# panel5.net
KiCad netlist of a schematic drawn in Altium Designer
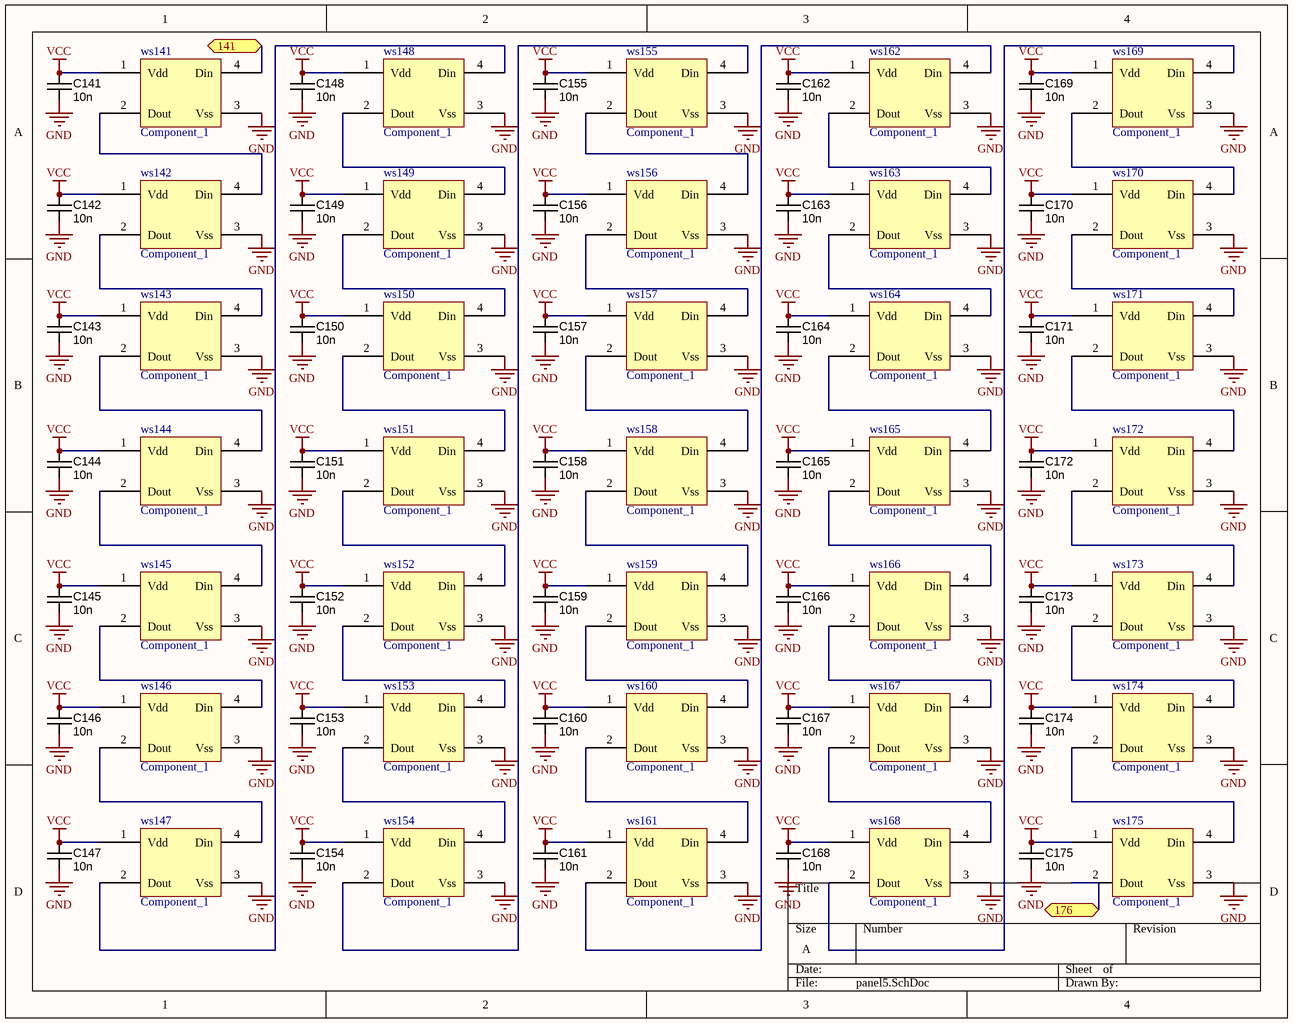
[diagram p0: panel5.SchDoc]

(export (version "E")
  (design (tool "Eeschema 10.0.6"))
  (components
    (comp (ref "C141")
      (value "10n")
      (footprint "CAPC1608X90N")
      (description "Capacitor SMD Cer 10nF 10% 100V X7R 0603")
      (fields
        (field (name "TOLERANCE") "±10%")
        (field (name "MANUFACTURER") "Murata Electronics North America")
      )
      (libsource (lib "PBL - Capacitors") (part "CAPC_10n_0603_X7R_100V_10%"))
    )
    (comp (ref "C142")
      (value "10n")
      (footprint "CAPC1608X90N")
      (description "Capacitor SMD Cer 10nF 10% 100V X7R 0603")
      (fields
        (field (name "TOLERANCE") "±10%")
        (field (name "MANUFACTURER") "Murata Electronics North America")
      )
      (libsource (lib "PBL - Capacitors") (part "CAPC_10n_0603_X7R_100V_10%"))
    )
    (comp (ref "C143")
      (value "10n")
      (footprint "CAPC1608X90N")
      (description "Capacitor SMD Cer 10nF 10% 100V X7R 0603")
      (fields
        (field (name "TOLERANCE") "±10%")
        (field (name "MANUFACTURER") "Murata Electronics North America")
      )
      (libsource (lib "PBL - Capacitors") (part "CAPC_10n_0603_X7R_100V_10%"))
    )
    (comp (ref "C144")
      (value "10n")
      (footprint "CAPC1608X90N")
      (description "Capacitor SMD Cer 10nF 10% 100V X7R 0603")
      (fields
        (field (name "TOLERANCE") "±10%")
        (field (name "MANUFACTURER") "Murata Electronics North America")
      )
      (libsource (lib "PBL - Capacitors") (part "CAPC_10n_0603_X7R_100V_10%"))
    )
    (comp (ref "C145")
      (value "10n")
      (footprint "CAPC1608X90N")
      (description "Capacitor SMD Cer 10nF 10% 100V X7R 0603")
      (fields
        (field (name "TOLERANCE") "±10%")
        (field (name "MANUFACTURER") "Murata Electronics North America")
      )
      (libsource (lib "PBL - Capacitors") (part "CAPC_10n_0603_X7R_100V_10%"))
    )
    (comp (ref "C146")
      (value "10n")
      (footprint "CAPC1608X90N")
      (description "Capacitor SMD Cer 10nF 10% 100V X7R 0603")
      (fields
        (field (name "TOLERANCE") "±10%")
        (field (name "MANUFACTURER") "Murata Electronics North America")
      )
      (libsource (lib "PBL - Capacitors") (part "CAPC_10n_0603_X7R_100V_10%"))
    )
    (comp (ref "C147")
      (value "10n")
      (footprint "CAPC1608X90N")
      (description "Capacitor SMD Cer 10nF 10% 100V X7R 0603")
      (fields
        (field (name "TOLERANCE") "±10%")
        (field (name "MANUFACTURER") "Murata Electronics North America")
      )
      (libsource (lib "PBL - Capacitors") (part "CAPC_10n_0603_X7R_100V_10%"))
    )
    (comp (ref "C148")
      (value "10n")
      (footprint "CAPC1608X90N")
      (description "Capacitor SMD Cer 10nF 10% 100V X7R 0603")
      (fields
        (field (name "TOLERANCE") "±10%")
        (field (name "MANUFACTURER") "Murata Electronics North America")
      )
      (libsource (lib "PBL - Capacitors") (part "CAPC_10n_0603_X7R_100V_10%"))
    )
    (comp (ref "C149")
      (value "10n")
      (footprint "CAPC1608X90N")
      (description "Capacitor SMD Cer 10nF 10% 100V X7R 0603")
      (fields
        (field (name "TOLERANCE") "±10%")
        (field (name "MANUFACTURER") "Murata Electronics North America")
      )
      (libsource (lib "PBL - Capacitors") (part "CAPC_10n_0603_X7R_100V_10%"))
    )
    (comp (ref "C150")
      (value "10n")
      (footprint "CAPC1608X90N")
      (description "Capacitor SMD Cer 10nF 10% 100V X7R 0603")
      (fields
        (field (name "TOLERANCE") "±10%")
        (field (name "MANUFACTURER") "Murata Electronics North America")
      )
      (libsource (lib "PBL - Capacitors") (part "CAPC_10n_0603_X7R_100V_10%"))
    )
    (comp (ref "C151")
      (value "10n")
      (footprint "CAPC1608X90N")
      (description "Capacitor SMD Cer 10nF 10% 100V X7R 0603")
      (fields
        (field (name "TOLERANCE") "±10%")
        (field (name "MANUFACTURER") "Murata Electronics North America")
      )
      (libsource (lib "PBL - Capacitors") (part "CAPC_10n_0603_X7R_100V_10%"))
    )
    (comp (ref "C152")
      (value "10n")
      (footprint "CAPC1608X90N")
      (description "Capacitor SMD Cer 10nF 10% 100V X7R 0603")
      (fields
        (field (name "TOLERANCE") "±10%")
        (field (name "MANUFACTURER") "Murata Electronics North America")
      )
      (libsource (lib "PBL - Capacitors") (part "CAPC_10n_0603_X7R_100V_10%"))
    )
    (comp (ref "C153")
      (value "10n")
      (footprint "CAPC1608X90N")
      (description "Capacitor SMD Cer 10nF 10% 100V X7R 0603")
      (fields
        (field (name "TOLERANCE") "±10%")
        (field (name "MANUFACTURER") "Murata Electronics North America")
      )
      (libsource (lib "PBL - Capacitors") (part "CAPC_10n_0603_X7R_100V_10%"))
    )
    (comp (ref "C154")
      (value "10n")
      (footprint "CAPC1608X90N")
      (description "Capacitor SMD Cer 10nF 10% 100V X7R 0603")
      (fields
        (field (name "TOLERANCE") "±10%")
        (field (name "MANUFACTURER") "Murata Electronics North America")
      )
      (libsource (lib "PBL - Capacitors") (part "CAPC_10n_0603_X7R_100V_10%"))
    )
    (comp (ref "C155")
      (value "10n")
      (footprint "CAPC1608X90N")
      (description "Capacitor SMD Cer 10nF 10% 100V X7R 0603")
      (fields
        (field (name "TOLERANCE") "±10%")
        (field (name "MANUFACTURER") "Murata Electronics North America")
      )
      (libsource (lib "PBL - Capacitors") (part "CAPC_10n_0603_X7R_100V_10%"))
    )
    (comp (ref "C156")
      (value "10n")
      (footprint "CAPC1608X90N")
      (description "Capacitor SMD Cer 10nF 10% 100V X7R 0603")
      (fields
        (field (name "TOLERANCE") "±10%")
        (field (name "MANUFACTURER") "Murata Electronics North America")
      )
      (libsource (lib "PBL - Capacitors") (part "CAPC_10n_0603_X7R_100V_10%"))
    )
    (comp (ref "C157")
      (value "10n")
      (footprint "CAPC1608X90N")
      (description "Capacitor SMD Cer 10nF 10% 100V X7R 0603")
      (fields
        (field (name "TOLERANCE") "±10%")
        (field (name "MANUFACTURER") "Murata Electronics North America")
      )
      (libsource (lib "PBL - Capacitors") (part "CAPC_10n_0603_X7R_100V_10%"))
    )
    (comp (ref "C158")
      (value "10n")
      (footprint "CAPC1608X90N")
      (description "Capacitor SMD Cer 10nF 10% 100V X7R 0603")
      (fields
        (field (name "TOLERANCE") "±10%")
        (field (name "MANUFACTURER") "Murata Electronics North America")
      )
      (libsource (lib "PBL - Capacitors") (part "CAPC_10n_0603_X7R_100V_10%"))
    )
    (comp (ref "C159")
      (value "10n")
      (footprint "CAPC1608X90N")
      (description "Capacitor SMD Cer 10nF 10% 100V X7R 0603")
      (fields
        (field (name "TOLERANCE") "±10%")
        (field (name "MANUFACTURER") "Murata Electronics North America")
      )
      (libsource (lib "PBL - Capacitors") (part "CAPC_10n_0603_X7R_100V_10%"))
    )
    (comp (ref "C160")
      (value "10n")
      (footprint "CAPC1608X90N")
      (description "Capacitor SMD Cer 10nF 10% 100V X7R 0603")
      (fields
        (field (name "TOLERANCE") "±10%")
        (field (name "MANUFACTURER") "Murata Electronics North America")
      )
      (libsource (lib "PBL - Capacitors") (part "CAPC_10n_0603_X7R_100V_10%"))
    )
    (comp (ref "C161")
      (value "10n")
      (footprint "CAPC1608X90N")
      (description "Capacitor SMD Cer 10nF 10% 100V X7R 0603")
      (fields
        (field (name "TOLERANCE") "±10%")
        (field (name "MANUFACTURER") "Murata Electronics North America")
      )
      (libsource (lib "PBL - Capacitors") (part "CAPC_10n_0603_X7R_100V_10%"))
    )
    (comp (ref "C162")
      (value "10n")
      (footprint "CAPC1608X90N")
      (description "Capacitor SMD Cer 10nF 10% 100V X7R 0603")
      (fields
        (field (name "TOLERANCE") "±10%")
        (field (name "MANUFACTURER") "Murata Electronics North America")
      )
      (libsource (lib "PBL - Capacitors") (part "CAPC_10n_0603_X7R_100V_10%"))
    )
    (comp (ref "C163")
      (value "10n")
      (footprint "CAPC1608X90N")
      (description "Capacitor SMD Cer 10nF 10% 100V X7R 0603")
      (fields
        (field (name "TOLERANCE") "±10%")
        (field (name "MANUFACTURER") "Murata Electronics North America")
      )
      (libsource (lib "PBL - Capacitors") (part "CAPC_10n_0603_X7R_100V_10%"))
    )
    (comp (ref "C164")
      (value "10n")
      (footprint "CAPC1608X90N")
      (description "Capacitor SMD Cer 10nF 10% 100V X7R 0603")
      (fields
        (field (name "TOLERANCE") "±10%")
        (field (name "MANUFACTURER") "Murata Electronics North America")
      )
      (libsource (lib "PBL - Capacitors") (part "CAPC_10n_0603_X7R_100V_10%"))
    )
    (comp (ref "C165")
      (value "10n")
      (footprint "CAPC1608X90N")
      (description "Capacitor SMD Cer 10nF 10% 100V X7R 0603")
      (fields
        (field (name "TOLERANCE") "±10%")
        (field (name "MANUFACTURER") "Murata Electronics North America")
      )
      (libsource (lib "PBL - Capacitors") (part "CAPC_10n_0603_X7R_100V_10%"))
    )
    (comp (ref "C166")
      (value "10n")
      (footprint "CAPC1608X90N")
      (description "Capacitor SMD Cer 10nF 10% 100V X7R 0603")
      (fields
        (field (name "TOLERANCE") "±10%")
        (field (name "MANUFACTURER") "Murata Electronics North America")
      )
      (libsource (lib "PBL - Capacitors") (part "CAPC_10n_0603_X7R_100V_10%"))
    )
    (comp (ref "C167")
      (value "10n")
      (footprint "CAPC1608X90N")
      (description "Capacitor SMD Cer 10nF 10% 100V X7R 0603")
      (fields
        (field (name "TOLERANCE") "±10%")
        (field (name "MANUFACTURER") "Murata Electronics North America")
      )
      (libsource (lib "PBL - Capacitors") (part "CAPC_10n_0603_X7R_100V_10%"))
    )
    (comp (ref "C168")
      (value "10n")
      (footprint "CAPC1608X90N")
      (description "Capacitor SMD Cer 10nF 10% 100V X7R 0603")
      (fields
        (field (name "TOLERANCE") "±10%")
        (field (name "MANUFACTURER") "Murata Electronics North America")
      )
      (libsource (lib "PBL - Capacitors") (part "CAPC_10n_0603_X7R_100V_10%"))
    )
    (comp (ref "C169")
      (value "10n")
      (footprint "CAPC1608X90N")
      (description "Capacitor SMD Cer 10nF 10% 100V X7R 0603")
      (fields
        (field (name "TOLERANCE") "±10%")
        (field (name "MANUFACTURER") "Murata Electronics North America")
      )
      (libsource (lib "PBL - Capacitors") (part "CAPC_10n_0603_X7R_100V_10%"))
    )
    (comp (ref "C170")
      (value "10n")
      (footprint "CAPC1608X90N")
      (description "Capacitor SMD Cer 10nF 10% 100V X7R 0603")
      (fields
        (field (name "TOLERANCE") "±10%")
        (field (name "MANUFACTURER") "Murata Electronics North America")
      )
      (libsource (lib "PBL - Capacitors") (part "CAPC_10n_0603_X7R_100V_10%"))
    )
    (comp (ref "C171")
      (value "10n")
      (footprint "CAPC1608X90N")
      (description "Capacitor SMD Cer 10nF 10% 100V X7R 0603")
      (fields
        (field (name "TOLERANCE") "±10%")
        (field (name "MANUFACTURER") "Murata Electronics North America")
      )
      (libsource (lib "PBL - Capacitors") (part "CAPC_10n_0603_X7R_100V_10%"))
    )
    (comp (ref "C172")
      (value "10n")
      (footprint "CAPC1608X90N")
      (description "Capacitor SMD Cer 10nF 10% 100V X7R 0603")
      (fields
        (field (name "TOLERANCE") "±10%")
        (field (name "MANUFACTURER") "Murata Electronics North America")
      )
      (libsource (lib "PBL - Capacitors") (part "CAPC_10n_0603_X7R_100V_10%"))
    )
    (comp (ref "C173")
      (value "10n")
      (footprint "CAPC1608X90N")
      (description "Capacitor SMD Cer 10nF 10% 100V X7R 0603")
      (fields
        (field (name "TOLERANCE") "±10%")
        (field (name "MANUFACTURER") "Murata Electronics North America")
      )
      (libsource (lib "PBL - Capacitors") (part "CAPC_10n_0603_X7R_100V_10%"))
    )
    (comp (ref "C174")
      (value "10n")
      (footprint "CAPC1608X90N")
      (description "Capacitor SMD Cer 10nF 10% 100V X7R 0603")
      (fields
        (field (name "TOLERANCE") "±10%")
        (field (name "MANUFACTURER") "Murata Electronics North America")
      )
      (libsource (lib "PBL - Capacitors") (part "CAPC_10n_0603_X7R_100V_10%"))
    )
    (comp (ref "C175")
      (value "10n")
      (footprint "CAPC1608X90N")
      (description "Capacitor SMD Cer 10nF 10% 100V X7R 0603")
      (fields
        (field (name "TOLERANCE") "±10%")
        (field (name "MANUFACTURER") "Murata Electronics North America")
      )
      (libsource (lib "PBL - Capacitors") (part "CAPC_10n_0603_X7R_100V_10%"))
    )
    (comp (ref "ws141")
      (value "Component_1")
      (footprint "SOP4")
      (libsource (lib "ws2812b") (part "Component_1"))
    )
    (comp (ref "ws142")
      (value "Component_1")
      (footprint "SOP4")
      (libsource (lib "ws2812b") (part "Component_1"))
    )
    (comp (ref "ws143")
      (value "Component_1")
      (footprint "SOP4")
      (libsource (lib "ws2812b") (part "Component_1"))
    )
    (comp (ref "ws144")
      (value "Component_1")
      (footprint "SOP4")
      (libsource (lib "ws2812b") (part "Component_1"))
    )
    (comp (ref "ws145")
      (value "Component_1")
      (footprint "SOP4")
      (libsource (lib "ws2812b") (part "Component_1"))
    )
    (comp (ref "ws146")
      (value "Component_1")
      (footprint "SOP4")
      (libsource (lib "ws2812b") (part "Component_1"))
    )
    (comp (ref "ws147")
      (value "Component_1")
      (footprint "SOP4")
      (libsource (lib "ws2812b") (part "Component_1"))
    )
    (comp (ref "ws148")
      (value "Component_1")
      (footprint "SOP4")
      (libsource (lib "ws2812b") (part "Component_1"))
    )
    (comp (ref "ws149")
      (value "Component_1")
      (footprint "SOP4")
      (libsource (lib "ws2812b") (part "Component_1"))
    )
    (comp (ref "ws150")
      (value "Component_1")
      (footprint "SOP4")
      (libsource (lib "ws2812b") (part "Component_1"))
    )
    (comp (ref "ws151")
      (value "Component_1")
      (footprint "SOP4")
      (libsource (lib "ws2812b") (part "Component_1"))
    )
    (comp (ref "ws152")
      (value "Component_1")
      (footprint "SOP4")
      (libsource (lib "ws2812b") (part "Component_1"))
    )
    (comp (ref "ws153")
      (value "Component_1")
      (footprint "SOP4")
      (libsource (lib "ws2812b") (part "Component_1"))
    )
    (comp (ref "ws154")
      (value "Component_1")
      (footprint "SOP4")
      (libsource (lib "ws2812b") (part "Component_1"))
    )
    (comp (ref "ws155")
      (value "Component_1")
      (footprint "SOP4")
      (libsource (lib "ws2812b") (part "Component_1"))
    )
    (comp (ref "ws156")
      (value "Component_1")
      (footprint "SOP4")
      (libsource (lib "ws2812b") (part "Component_1"))
    )
    (comp (ref "ws157")
      (value "Component_1")
      (footprint "SOP4")
      (libsource (lib "ws2812b") (part "Component_1"))
    )
    (comp (ref "ws158")
      (value "Component_1")
      (footprint "SOP4")
      (libsource (lib "ws2812b") (part "Component_1"))
    )
    (comp (ref "ws159")
      (value "Component_1")
      (footprint "SOP4")
      (libsource (lib "ws2812b") (part "Component_1"))
    )
    (comp (ref "ws160")
      (value "Component_1")
      (footprint "SOP4")
      (libsource (lib "ws2812b") (part "Component_1"))
    )
    (comp (ref "ws161")
      (value "Component_1")
      (footprint "SOP4")
      (libsource (lib "ws2812b") (part "Component_1"))
    )
    (comp (ref "ws162")
      (value "Component_1")
      (footprint "SOP4")
      (libsource (lib "ws2812b") (part "Component_1"))
    )
    (comp (ref "ws163")
      (value "Component_1")
      (footprint "SOP4")
      (libsource (lib "ws2812b") (part "Component_1"))
    )
    (comp (ref "ws164")
      (value "Component_1")
      (footprint "SOP4")
      (libsource (lib "ws2812b") (part "Component_1"))
    )
    (comp (ref "ws165")
      (value "Component_1")
      (footprint "SOP4")
      (libsource (lib "ws2812b") (part "Component_1"))
    )
    (comp (ref "ws166")
      (value "Component_1")
      (footprint "SOP4")
      (libsource (lib "ws2812b") (part "Component_1"))
    )
    (comp (ref "ws167")
      (value "Component_1")
      (footprint "SOP4")
      (libsource (lib "ws2812b") (part "Component_1"))
    )
    (comp (ref "ws168")
      (value "Component_1")
      (footprint "SOP4")
      (libsource (lib "ws2812b") (part "Component_1"))
    )
    (comp (ref "ws169")
      (value "Component_1")
      (footprint "SOP4")
      (libsource (lib "ws2812b") (part "Component_1"))
    )
    (comp (ref "ws170")
      (value "Component_1")
      (footprint "SOP4")
      (libsource (lib "ws2812b") (part "Component_1"))
    )
    (comp (ref "ws171")
      (value "Component_1")
      (footprint "SOP4")
      (libsource (lib "ws2812b") (part "Component_1"))
    )
    (comp (ref "ws172")
      (value "Component_1")
      (footprint "SOP4")
      (libsource (lib "ws2812b") (part "Component_1"))
    )
    (comp (ref "ws173")
      (value "Component_1")
      (footprint "SOP4")
      (libsource (lib "ws2812b") (part "Component_1"))
    )
    (comp (ref "ws174")
      (value "Component_1")
      (footprint "SOP4")
      (libsource (lib "ws2812b") (part "Component_1"))
    )
    (comp (ref "ws175")
      (value "Component_1")
      (footprint "SOP4")
      (libsource (lib "ws2812b") (part "Component_1"))
    )
  )
  (nets
    (net (code "1") (name "/141") (class "Default")
      (node (ref "ws141") (pin "4") (pinfunction "Din_4") (pintype "passive"))
    )
    (net (code "2") (name "/176") (class "Default")
      (node (ref "ws175") (pin "2") (pinfunction "Dout_2") (pintype "passive"))
    )
    (net (code "3") (name "GND") (class "Default")
      (node (ref "C141") (pin "2") (pintype "passive"))
      (node (ref "C142") (pin "2") (pintype "passive"))
      (node (ref "C143") (pin "2") (pintype "passive"))
      (node (ref "C144") (pin "2") (pintype "passive"))
      (node (ref "C145") (pin "2") (pintype "passive"))
      (node (ref "C146") (pin "2") (pintype "passive"))
      (node (ref "C147") (pin "2") (pintype "passive"))
      (node (ref "C148") (pin "2") (pintype "passive"))
      (node (ref "C149") (pin "2") (pintype "passive"))
      (node (ref "C150") (pin "2") (pintype "passive"))
      (node (ref "C151") (pin "2") (pintype "passive"))
      (node (ref "C152") (pin "2") (pintype "passive"))
      (node (ref "C153") (pin "2") (pintype "passive"))
      (node (ref "C154") (pin "2") (pintype "passive"))
      (node (ref "C155") (pin "2") (pintype "passive"))
      (node (ref "C156") (pin "2") (pintype "passive"))
      (node (ref "C157") (pin "2") (pintype "passive"))
      (node (ref "C158") (pin "2") (pintype "passive"))
      (node (ref "C159") (pin "2") (pintype "passive"))
      (node (ref "C160") (pin "2") (pintype "passive"))
      (node (ref "C161") (pin "2") (pintype "passive"))
      (node (ref "C162") (pin "2") (pintype "passive"))
      (node (ref "C163") (pin "2") (pintype "passive"))
      (node (ref "C164") (pin "2") (pintype "passive"))
      (node (ref "C165") (pin "2") (pintype "passive"))
      (node (ref "C166") (pin "2") (pintype "passive"))
      (node (ref "C167") (pin "2") (pintype "passive"))
      (node (ref "C168") (pin "2") (pintype "passive"))
      (node (ref "C169") (pin "2") (pintype "passive"))
      (node (ref "C170") (pin "2") (pintype "passive"))
      (node (ref "C171") (pin "2") (pintype "passive"))
      (node (ref "C172") (pin "2") (pintype "passive"))
      (node (ref "C173") (pin "2") (pintype "passive"))
      (node (ref "C174") (pin "2") (pintype "passive"))
      (node (ref "C175") (pin "2") (pintype "passive"))
      (node (ref "ws141") (pin "3") (pinfunction "Vss_3") (pintype "passive"))
      (node (ref "ws142") (pin "3") (pinfunction "Vss_3") (pintype "passive"))
      (node (ref "ws143") (pin "3") (pinfunction "Vss_3") (pintype "passive"))
      (node (ref "ws144") (pin "3") (pinfunction "Vss_3") (pintype "passive"))
      (node (ref "ws145") (pin "3") (pinfunction "Vss_3") (pintype "passive"))
      (node (ref "ws146") (pin "3") (pinfunction "Vss_3") (pintype "passive"))
      (node (ref "ws147") (pin "3") (pinfunction "Vss_3") (pintype "passive"))
      (node (ref "ws148") (pin "3") (pinfunction "Vss_3") (pintype "passive"))
      (node (ref "ws149") (pin "3") (pinfunction "Vss_3") (pintype "passive"))
      (node (ref "ws150") (pin "3") (pinfunction "Vss_3") (pintype "passive"))
      (node (ref "ws151") (pin "3") (pinfunction "Vss_3") (pintype "passive"))
      (node (ref "ws152") (pin "3") (pinfunction "Vss_3") (pintype "passive"))
      (node (ref "ws153") (pin "3") (pinfunction "Vss_3") (pintype "passive"))
      (node (ref "ws154") (pin "3") (pinfunction "Vss_3") (pintype "passive"))
      (node (ref "ws155") (pin "3") (pinfunction "Vss_3") (pintype "passive"))
      (node (ref "ws156") (pin "3") (pinfunction "Vss_3") (pintype "passive"))
      (node (ref "ws157") (pin "3") (pinfunction "Vss_3") (pintype "passive"))
      (node (ref "ws158") (pin "3") (pinfunction "Vss_3") (pintype "passive"))
      (node (ref "ws159") (pin "3") (pinfunction "Vss_3") (pintype "passive"))
      (node (ref "ws160") (pin "3") (pinfunction "Vss_3") (pintype "passive"))
      (node (ref "ws161") (pin "3") (pinfunction "Vss_3") (pintype "passive"))
      (node (ref "ws162") (pin "3") (pinfunction "Vss_3") (pintype "passive"))
      (node (ref "ws163") (pin "3") (pinfunction "Vss_3") (pintype "passive"))
      (node (ref "ws164") (pin "3") (pinfunction "Vss_3") (pintype "passive"))
      (node (ref "ws165") (pin "3") (pinfunction "Vss_3") (pintype "passive"))
      (node (ref "ws166") (pin "3") (pinfunction "Vss_3") (pintype "passive"))
      (node (ref "ws167") (pin "3") (pinfunction "Vss_3") (pintype "passive"))
      (node (ref "ws168") (pin "3") (pinfunction "Vss_3") (pintype "passive"))
      (node (ref "ws169") (pin "3") (pinfunction "Vss_3") (pintype "passive"))
      (node (ref "ws170") (pin "3") (pinfunction "Vss_3") (pintype "passive"))
      (node (ref "ws171") (pin "3") (pinfunction "Vss_3") (pintype "passive"))
      (node (ref "ws172") (pin "3") (pinfunction "Vss_3") (pintype "passive"))
      (node (ref "ws173") (pin "3") (pinfunction "Vss_3") (pintype "passive"))
      (node (ref "ws174") (pin "3") (pinfunction "Vss_3") (pintype "passive"))
      (node (ref "ws175") (pin "3") (pinfunction "Vss_3") (pintype "passive"))
    )
    (net (code "4") (name "Net-(ws141-Dout)") (class "Default")
      (node (ref "ws141") (pin "2") (pinfunction "Dout_2") (pintype "passive"))
      (node (ref "ws142") (pin "4") (pinfunction "Din_4") (pintype "passive"))
    )
    (net (code "5") (name "Net-(ws142-Dout)") (class "Default")
      (node (ref "ws142") (pin "2") (pinfunction "Dout_2") (pintype "passive"))
      (node (ref "ws143") (pin "4") (pinfunction "Din_4") (pintype "passive"))
    )
    (net (code "6") (name "Net-(ws143-Dout)") (class "Default")
      (node (ref "ws143") (pin "2") (pinfunction "Dout_2") (pintype "passive"))
      (node (ref "ws144") (pin "4") (pinfunction "Din_4") (pintype "passive"))
    )
    (net (code "7") (name "Net-(ws144-Dout)") (class "Default")
      (node (ref "ws144") (pin "2") (pinfunction "Dout_2") (pintype "passive"))
      (node (ref "ws145") (pin "4") (pinfunction "Din_4") (pintype "passive"))
    )
    (net (code "8") (name "Net-(ws145-Dout)") (class "Default")
      (node (ref "ws145") (pin "2") (pinfunction "Dout_2") (pintype "passive"))
      (node (ref "ws146") (pin "4") (pinfunction "Din_4") (pintype "passive"))
    )
    (net (code "9") (name "Net-(ws146-Dout)") (class "Default")
      (node (ref "ws146") (pin "2") (pinfunction "Dout_2") (pintype "passive"))
      (node (ref "ws147") (pin "4") (pinfunction "Din_4") (pintype "passive"))
    )
    (net (code "10") (name "Net-(ws147-Dout)") (class "Default")
      (node (ref "ws147") (pin "2") (pinfunction "Dout_2") (pintype "passive"))
      (node (ref "ws148") (pin "4") (pinfunction "Din_4") (pintype "passive"))
    )
    (net (code "11") (name "Net-(ws148-Dout)") (class "Default")
      (node (ref "ws148") (pin "2") (pinfunction "Dout_2") (pintype "passive"))
      (node (ref "ws149") (pin "4") (pinfunction "Din_4") (pintype "passive"))
    )
    (net (code "12") (name "Net-(ws149-Dout)") (class "Default")
      (node (ref "ws149") (pin "2") (pinfunction "Dout_2") (pintype "passive"))
      (node (ref "ws150") (pin "4") (pinfunction "Din_4") (pintype "passive"))
    )
    (net (code "13") (name "Net-(ws150-Dout)") (class "Default")
      (node (ref "ws150") (pin "2") (pinfunction "Dout_2") (pintype "passive"))
      (node (ref "ws151") (pin "4") (pinfunction "Din_4") (pintype "passive"))
    )
    (net (code "14") (name "Net-(ws151-Dout)") (class "Default")
      (node (ref "ws151") (pin "2") (pinfunction "Dout_2") (pintype "passive"))
      (node (ref "ws152") (pin "4") (pinfunction "Din_4") (pintype "passive"))
    )
    (net (code "15") (name "Net-(ws152-Dout)") (class "Default")
      (node (ref "ws152") (pin "2") (pinfunction "Dout_2") (pintype "passive"))
      (node (ref "ws153") (pin "4") (pinfunction "Din_4") (pintype "passive"))
    )
    (net (code "16") (name "Net-(ws153-Dout)") (class "Default")
      (node (ref "ws153") (pin "2") (pinfunction "Dout_2") (pintype "passive"))
      (node (ref "ws154") (pin "4") (pinfunction "Din_4") (pintype "passive"))
    )
    (net (code "17") (name "Net-(ws154-Dout)") (class "Default")
      (node (ref "ws154") (pin "2") (pinfunction "Dout_2") (pintype "passive"))
      (node (ref "ws155") (pin "4") (pinfunction "Din_4") (pintype "passive"))
    )
    (net (code "18") (name "Net-(ws155-Dout)") (class "Default")
      (node (ref "ws155") (pin "2") (pinfunction "Dout_2") (pintype "passive"))
      (node (ref "ws156") (pin "4") (pinfunction "Din_4") (pintype "passive"))
    )
    (net (code "19") (name "Net-(ws156-Dout)") (class "Default")
      (node (ref "ws156") (pin "2") (pinfunction "Dout_2") (pintype "passive"))
      (node (ref "ws157") (pin "4") (pinfunction "Din_4") (pintype "passive"))
    )
    (net (code "20") (name "Net-(ws157-Dout)") (class "Default")
      (node (ref "ws157") (pin "2") (pinfunction "Dout_2") (pintype "passive"))
      (node (ref "ws158") (pin "4") (pinfunction "Din_4") (pintype "passive"))
    )
    (net (code "21") (name "Net-(ws158-Dout)") (class "Default")
      (node (ref "ws158") (pin "2") (pinfunction "Dout_2") (pintype "passive"))
      (node (ref "ws159") (pin "4") (pinfunction "Din_4") (pintype "passive"))
    )
    (net (code "22") (name "Net-(ws159-Dout)") (class "Default")
      (node (ref "ws159") (pin "2") (pinfunction "Dout_2") (pintype "passive"))
      (node (ref "ws160") (pin "4") (pinfunction "Din_4") (pintype "passive"))
    )
    (net (code "23") (name "Net-(ws160-Dout)") (class "Default")
      (node (ref "ws160") (pin "2") (pinfunction "Dout_2") (pintype "passive"))
      (node (ref "ws161") (pin "4") (pinfunction "Din_4") (pintype "passive"))
    )
    (net (code "24") (name "Net-(ws161-Dout)") (class "Default")
      (node (ref "ws161") (pin "2") (pinfunction "Dout_2") (pintype "passive"))
      (node (ref "ws162") (pin "4") (pinfunction "Din_4") (pintype "passive"))
    )
    (net (code "25") (name "Net-(ws162-Dout)") (class "Default")
      (node (ref "ws162") (pin "2") (pinfunction "Dout_2") (pintype "passive"))
      (node (ref "ws163") (pin "4") (pinfunction "Din_4") (pintype "passive"))
    )
    (net (code "26") (name "Net-(ws163-Dout)") (class "Default")
      (node (ref "ws163") (pin "2") (pinfunction "Dout_2") (pintype "passive"))
      (node (ref "ws164") (pin "4") (pinfunction "Din_4") (pintype "passive"))
    )
    (net (code "27") (name "Net-(ws164-Dout)") (class "Default")
      (node (ref "ws164") (pin "2") (pinfunction "Dout_2") (pintype "passive"))
      (node (ref "ws165") (pin "4") (pinfunction "Din_4") (pintype "passive"))
    )
    (net (code "28") (name "Net-(ws165-Dout)") (class "Default")
      (node (ref "ws165") (pin "2") (pinfunction "Dout_2") (pintype "passive"))
      (node (ref "ws166") (pin "4") (pinfunction "Din_4") (pintype "passive"))
    )
    (net (code "29") (name "Net-(ws166-Dout)") (class "Default")
      (node (ref "ws166") (pin "2") (pinfunction "Dout_2") (pintype "passive"))
      (node (ref "ws167") (pin "4") (pinfunction "Din_4") (pintype "passive"))
    )
    (net (code "30") (name "Net-(ws167-Dout)") (class "Default")
      (node (ref "ws167") (pin "2") (pinfunction "Dout_2") (pintype "passive"))
      (node (ref "ws168") (pin "4") (pinfunction "Din_4") (pintype "passive"))
    )
    (net (code "31") (name "Net-(ws168-Dout)") (class "Default")
      (node (ref "ws168") (pin "2") (pinfunction "Dout_2") (pintype "passive"))
      (node (ref "ws169") (pin "4") (pinfunction "Din_4") (pintype "passive"))
    )
    (net (code "32") (name "Net-(ws169-Dout)") (class "Default")
      (node (ref "ws169") (pin "2") (pinfunction "Dout_2") (pintype "passive"))
      (node (ref "ws170") (pin "4") (pinfunction "Din_4") (pintype "passive"))
    )
    (net (code "33") (name "Net-(ws170-Dout)") (class "Default")
      (node (ref "ws170") (pin "2") (pinfunction "Dout_2") (pintype "passive"))
      (node (ref "ws171") (pin "4") (pinfunction "Din_4") (pintype "passive"))
    )
    (net (code "34") (name "Net-(ws171-Dout)") (class "Default")
      (node (ref "ws171") (pin "2") (pinfunction "Dout_2") (pintype "passive"))
      (node (ref "ws172") (pin "4") (pinfunction "Din_4") (pintype "passive"))
    )
    (net (code "35") (name "Net-(ws172-Dout)") (class "Default")
      (node (ref "ws172") (pin "2") (pinfunction "Dout_2") (pintype "passive"))
      (node (ref "ws173") (pin "4") (pinfunction "Din_4") (pintype "passive"))
    )
    (net (code "36") (name "Net-(ws173-Dout)") (class "Default")
      (node (ref "ws173") (pin "2") (pinfunction "Dout_2") (pintype "passive"))
      (node (ref "ws174") (pin "4") (pinfunction "Din_4") (pintype "passive"))
    )
    (net (code "37") (name "Net-(ws174-Dout)") (class "Default")
      (node (ref "ws174") (pin "2") (pinfunction "Dout_2") (pintype "passive"))
      (node (ref "ws175") (pin "4") (pinfunction "Din_4") (pintype "passive"))
    )
    (net (code "38") (name "VCC") (class "Default")
      (node (ref "C141") (pin "1") (pintype "passive"))
      (node (ref "C142") (pin "1") (pintype "passive"))
      (node (ref "C143") (pin "1") (pintype "passive"))
      (node (ref "C144") (pin "1") (pintype "passive"))
      (node (ref "C145") (pin "1") (pintype "passive"))
      (node (ref "C146") (pin "1") (pintype "passive"))
      (node (ref "C147") (pin "1") (pintype "passive"))
      (node (ref "C148") (pin "1") (pintype "passive"))
      (node (ref "C149") (pin "1") (pintype "passive"))
      (node (ref "C150") (pin "1") (pintype "passive"))
      (node (ref "C151") (pin "1") (pintype "passive"))
      (node (ref "C152") (pin "1") (pintype "passive"))
      (node (ref "C153") (pin "1") (pintype "passive"))
      (node (ref "C154") (pin "1") (pintype "passive"))
      (node (ref "C155") (pin "1") (pintype "passive"))
      (node (ref "C156") (pin "1") (pintype "passive"))
      (node (ref "C157") (pin "1") (pintype "passive"))
      (node (ref "C158") (pin "1") (pintype "passive"))
      (node (ref "C159") (pin "1") (pintype "passive"))
      (node (ref "C160") (pin "1") (pintype "passive"))
      (node (ref "C161") (pin "1") (pintype "passive"))
      (node (ref "C162") (pin "1") (pintype "passive"))
      (node (ref "C163") (pin "1") (pintype "passive"))
      (node (ref "C164") (pin "1") (pintype "passive"))
      (node (ref "C165") (pin "1") (pintype "passive"))
      (node (ref "C166") (pin "1") (pintype "passive"))
      (node (ref "C167") (pin "1") (pintype "passive"))
      (node (ref "C168") (pin "1") (pintype "passive"))
      (node (ref "C169") (pin "1") (pintype "passive"))
      (node (ref "C170") (pin "1") (pintype "passive"))
      (node (ref "C171") (pin "1") (pintype "passive"))
      (node (ref "C172") (pin "1") (pintype "passive"))
      (node (ref "C173") (pin "1") (pintype "passive"))
      (node (ref "C174") (pin "1") (pintype "passive"))
      (node (ref "C175") (pin "1") (pintype "passive"))
      (node (ref "ws141") (pin "1") (pinfunction "Vdd_1") (pintype "passive"))
      (node (ref "ws142") (pin "1") (pinfunction "Vdd_1") (pintype "passive"))
      (node (ref "ws143") (pin "1") (pinfunction "Vdd_1") (pintype "passive"))
      (node (ref "ws144") (pin "1") (pinfunction "Vdd_1") (pintype "passive"))
      (node (ref "ws145") (pin "1") (pinfunction "Vdd_1") (pintype "passive"))
      (node (ref "ws146") (pin "1") (pinfunction "Vdd_1") (pintype "passive"))
      (node (ref "ws147") (pin "1") (pinfunction "Vdd_1") (pintype "passive"))
      (node (ref "ws148") (pin "1") (pinfunction "Vdd_1") (pintype "passive"))
      (node (ref "ws149") (pin "1") (pinfunction "Vdd_1") (pintype "passive"))
      (node (ref "ws150") (pin "1") (pinfunction "Vdd_1") (pintype "passive"))
      (node (ref "ws151") (pin "1") (pinfunction "Vdd_1") (pintype "passive"))
      (node (ref "ws152") (pin "1") (pinfunction "Vdd_1") (pintype "passive"))
      (node (ref "ws153") (pin "1") (pinfunction "Vdd_1") (pintype "passive"))
      (node (ref "ws154") (pin "1") (pinfunction "Vdd_1") (pintype "passive"))
      (node (ref "ws155") (pin "1") (pinfunction "Vdd_1") (pintype "passive"))
      (node (ref "ws156") (pin "1") (pinfunction "Vdd_1") (pintype "passive"))
      (node (ref "ws157") (pin "1") (pinfunction "Vdd_1") (pintype "passive"))
      (node (ref "ws158") (pin "1") (pinfunction "Vdd_1") (pintype "passive"))
      (node (ref "ws159") (pin "1") (pinfunction "Vdd_1") (pintype "passive"))
      (node (ref "ws160") (pin "1") (pinfunction "Vdd_1") (pintype "passive"))
      (node (ref "ws161") (pin "1") (pinfunction "Vdd_1") (pintype "passive"))
      (node (ref "ws162") (pin "1") (pinfunction "Vdd_1") (pintype "passive"))
      (node (ref "ws163") (pin "1") (pinfunction "Vdd_1") (pintype "passive"))
      (node (ref "ws164") (pin "1") (pinfunction "Vdd_1") (pintype "passive"))
      (node (ref "ws165") (pin "1") (pinfunction "Vdd_1") (pintype "passive"))
      (node (ref "ws166") (pin "1") (pinfunction "Vdd_1") (pintype "passive"))
      (node (ref "ws167") (pin "1") (pinfunction "Vdd_1") (pintype "passive"))
      (node (ref "ws168") (pin "1") (pinfunction "Vdd_1") (pintype "passive"))
      (node (ref "ws169") (pin "1") (pinfunction "Vdd_1") (pintype "passive"))
      (node (ref "ws170") (pin "1") (pinfunction "Vdd_1") (pintype "passive"))
      (node (ref "ws171") (pin "1") (pinfunction "Vdd_1") (pintype "passive"))
      (node (ref "ws172") (pin "1") (pinfunction "Vdd_1") (pintype "passive"))
      (node (ref "ws173") (pin "1") (pinfunction "Vdd_1") (pintype "passive"))
      (node (ref "ws174") (pin "1") (pinfunction "Vdd_1") (pintype "passive"))
      (node (ref "ws175") (pin "1") (pinfunction "Vdd_1") (pintype "passive"))
    )
  )
)
